# First.net
KiCad netlist of a schematic drawn in Altium Designer
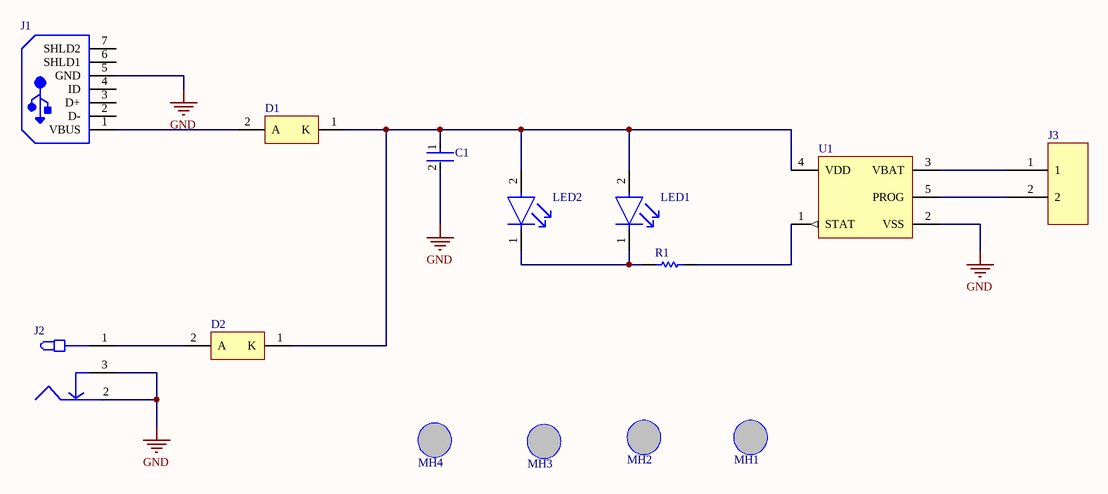
[diagram p0: First.SchDoc]

(export (version "E")
  (design (tool "Eeschema 10.0.6"))
  (components
    (comp (ref "C1")
      (value "EMK325B7475MN-T")
      (footprint "FP-1210-L_3_2_0_3-W_2_5_0-IPC_B")
      (description "None")
      (fields (field (name "VOLTAGE") "16V") (field (name "TOLERANCE") "20%"))
      (libsource (lib "Altium Content Vault") (part "02cd4be3c70576c341d710602a673aa"))
    )
    (comp (ref "D1")
      (value "MBRA140T3G")
      (footprint "ONSC-SMA-2-403D-02_V")
      (description "Schottky Power Rectifier, 2-Pin SMA, Pb-Free, Tape and Reel")
      (fields (field (name "MANUFACTURER") "On Semiconductor"))
      (libsource (lib "Altium Content Vault") (part "ONSC-D-K1A2-2_A"))
    )
    (comp (ref "D2")
      (value "MBRA140T3G")
      (footprint "ONSC-SMA-2-403D-02_V")
      (description "Schottky Power Rectifier, 2-Pin SMA, Pb-Free, Tape and Reel")
      (fields (field (name "MANUFACTURER") "On Semiconductor"))
      (libsource (lib "Altium Content Vault") (part "ONSC-D-K1A2-2_A"))
    )
    (comp (ref "J1")
      (value "USB3105-30-A")
      (footprint "GCT-USB3105-30-A_V")
      (description "USB 2.0 A/B Receptacle, 30 V, -55 to 85 degC, 5-Pin THD, RoHS, Tape and Reel")
      (fields (field (name "MANUFACTURER") "Global Connector Technology"))
      (libsource (lib "Altium Content Vault") (part "USB-5-2SHLD"))
    )
    (comp (ref "J2")
      (value "PJ-018H-SMT-TR")
      (footprint "FP-PJ-018H-SMT-TR-MFG")
      (description "CONN PWR JACK 1.7X4MM SOLDER")
      (fields
        (field (name "OCTOPART") "https://octopart.com/pj-018h-smt-tr-cui-25947163")
        (field (name "MANUFACTURER") "CUI")
      )
      (libsource (lib "Altium Content Vault") (part "69f6362642411a5d0af2144c195d2b5"))
    )
    (comp (ref "J3")
      (value "CONN HEADER R/A 2POS 5.08MM")
      (footprint "1-179276-2")
      (description "Connector Header Through Hole, Right Angle 2 position 0.200\" (5.08mm)")
      (fields
        (field (name "MANUFACTURER") "TE Connectivity AMP Connectors")
        (field (name "MANUFECTURER PART NUMBER") "1-179276-2")
      )
      (libsource (lib "First") (part "1-179276-2"))
    )
    (comp (ref "LED1")
      (value "SML-LX0603SIW-TR")
      (footprint "FP-SML-LX0603SIW-TR-MFG")
      (description "LED RED DIFFUSED SMD")
      (libsource (lib "Altium Content Vault") (part "8706943c75ba83719d021d2fdc84c58"))
    )
    (comp (ref "LED2")
      (value "SML-LX0603SIW-TR")
      (footprint "FP-SML-LX0603SIW-TR-MFG")
      (description "LED RED DIFFUSED SMD")
      (libsource (lib "Altium Content Vault") (part "8706943c75ba83719d021d2fdc84c58"))
    )
    (comp (ref "MH1")
      (value "Mounting Hole Non Plated")
      (footprint "Mounting Hole")
      (libsource (lib "First") (part "Mounting Hole"))
    )
    (comp (ref "MH2")
      (value "Mounting Hole Non Plated")
      (footprint "Mounting Hole")
      (libsource (lib "First") (part "Mounting Hole"))
    )
    (comp (ref "MH3")
      (value "Mounting Hole Non Plated")
      (footprint "Mounting Hole")
      (libsource (lib "First") (part "Mounting Hole"))
    )
    (comp (ref "MH4")
      (value "Mounting Hole Non Plated")
      (footprint "Mounting Hole")
      (libsource (lib "First") (part "Mounting Hole"))
    )
    (comp (ref "R1")
      (value "TFCR0805-10W-E-2001BT")
      (footprint "FP-TFCR0805-IPC_C")
      (fields (field (name "PART NUMBER") "RC0402JR-07330RL") (field (name "MANUFACTURER") "Yageo / Phycomp"))
      (libsource (lib "Altium Content Vault") (part "RES"))
    )
    (comp (ref "U1")
      (value "ESP32-PICO-V3")
      (footprint "SOT-23-OT5_N")
      (libsource (lib "Altium Content Vault") (part "PM-BM-MCP73831-SOT5"))
    )
  )
  (nets
    (net (code "1") (name "GND") (class "Default")
      (node (ref "C1") (pin "2") (pinfunction "2_2") (pintype "passive"))
      (node (ref "J1") (pin "5") (pinfunction "GND_5") (pintype "passive"))
      (node (ref "J2") (pin "2") (pinfunction "2_2") (pintype "passive"))
      (node (ref "J2") (pin "3") (pinfunction "3_3") (pintype "passive"))
      (node (ref "U1") (pin "2") (pinfunction "VSS_2") (pintype "power_in"))
    )
    (net (code "2") (name "Net-(D1-A)") (class "Default")
      (node (ref "D1") (pin "2") (pinfunction "A_2") (pintype "passive"))
      (node (ref "J1") (pin "1") (pinfunction "VBUS_1") (pintype "passive"))
    )
    (net (code "3") (name "Net-(D1-K)") (class "Default")
      (node (ref "C1") (pin "1") (pinfunction "1_1") (pintype "passive"))
      (node (ref "D1") (pin "1") (pinfunction "K_1") (pintype "passive"))
      (node (ref "D2") (pin "1") (pinfunction "K_1") (pintype "passive"))
      (node (ref "LED1") (pin "2") (pinfunction "A_2") (pintype "passive"))
      (node (ref "LED2") (pin "2") (pinfunction "A_2") (pintype "passive"))
      (node (ref "U1") (pin "4") (pinfunction "VDD_4") (pintype "power_in"))
    )
    (net (code "4") (name "Net-(D2-A)") (class "Default")
      (node (ref "D2") (pin "2") (pinfunction "A_2") (pintype "passive"))
      (node (ref "J2") (pin "1") (pinfunction "1_1") (pintype "passive"))
    )
    (net (code "5") (name "Net-(LED1-C)") (class "Default")
      (node (ref "LED1") (pin "1") (pinfunction "C_1") (pintype "passive"))
      (node (ref "LED2") (pin "1") (pinfunction "C_1") (pintype "passive"))
      (node (ref "R1") (pin "1") (pinfunction "1_1") (pintype "passive"))
    )
    (net (code "6") (name "Net-(U1-PROG)") (class "Default")
      (node (ref "J3") (pin "2") (pinfunction "2_2") (pintype "passive"))
      (node (ref "U1") (pin "5") (pinfunction "PROG_5") (pintype "passive"))
    )
    (net (code "7") (name "Net-(U1-STAT)") (class "Default")
      (node (ref "R1") (pin "2") (pinfunction "2_2") (pintype "passive"))
      (node (ref "U1") (pin "1") (pinfunction "STAT_1") (pintype "output"))
    )
    (net (code "8") (name "Net-(U1-VBAT)") (class "Default")
      (node (ref "J3") (pin "1") (pinfunction "1_1") (pintype "passive"))
      (node (ref "U1") (pin "3") (pinfunction "VBAT_3") (pintype "power_in"))
    )
    (net (code "9") (name "unconnected-(J1-D+-Pad3)") (class "Default")
      (node (ref "J1") (pin "3") (pinfunction "D+_3") (pintype "passive"))
    )
    (net (code "10") (name "unconnected-(J1-D--Pad2)") (class "Default")
      (node (ref "J1") (pin "2") (pinfunction "D-_2") (pintype "passive"))
    )
    (net (code "11") (name "unconnected-(J1-ID-Pad4)") (class "Default")
      (node (ref "J1") (pin "4") (pinfunction "ID_4") (pintype "passive"))
    )
    (net (code "12") (name "unconnected-(J1-SHLD1-Pad6)") (class "Default")
      (node (ref "J1") (pin "6") (pinfunction "SHLD1_6") (pintype "passive"))
    )
    (net (code "13") (name "unconnected-(J1-SHLD2-Pad7)") (class "Default")
      (node (ref "J1") (pin "7") (pinfunction "SHLD2_7") (pintype "passive"))
    )
  )
)
